# ME3116_3V3.net
KiCad netlist of a schematic drawn in Altium Designer
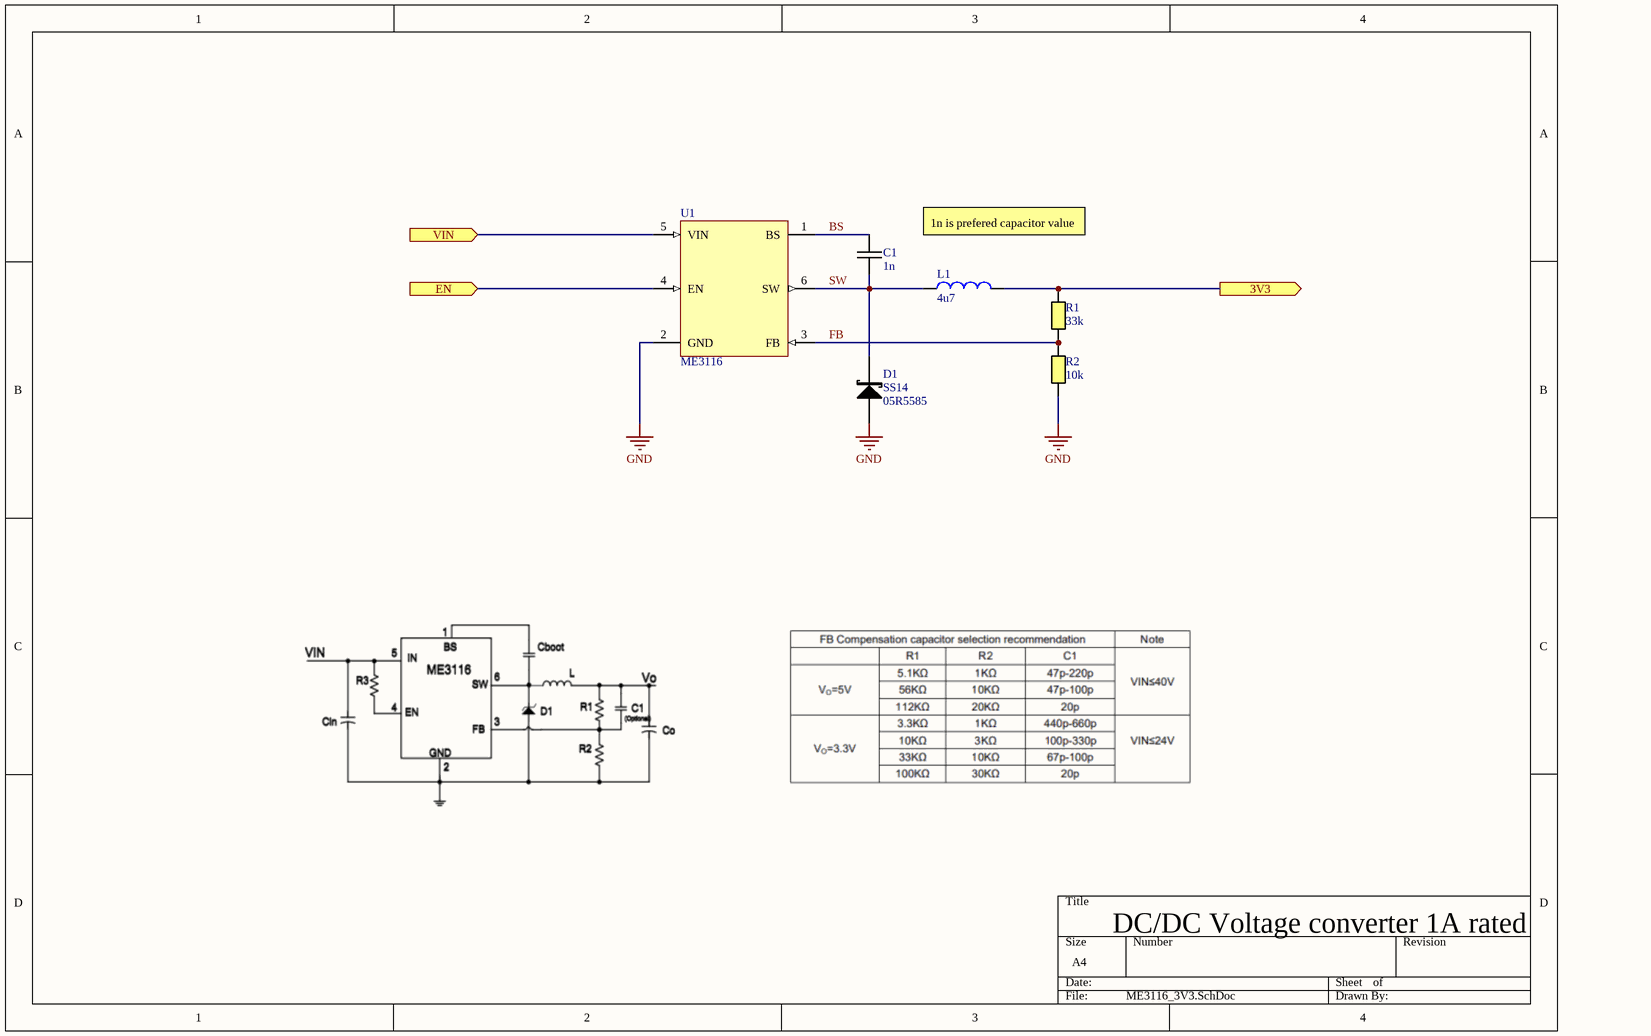
[diagram p0: ME3116_3V3.SchDoc]

(export (version "E")
  (design (tool "Eeschema 10.0.6"))
  (components
    (comp (ref "C1")
      (value "1n")
      (footprint "CAPC0603(1608)55_N")
      (description "Ceramic capacitor Medium density")
      (libsource (lib "Discrete") (part "Capacitor M"))
    )
    (comp (ref "D1")
      (value "SS14")
      (footprint "SMA")
      (description "Surface Mount Schottky Barrier Rectifier")
      (fields (field (name "SUPPLIER PART NUMBER 1") "05R5585"))
      (libsource (lib "Diodes") (part "SS14"))
    )
    (comp (ref "L1") (value "4u7") (footprint "CD75") (libsource (lib "Discrete") (part "Inductor")))
    (comp (ref "R1")
      (value "33k")
      (footprint "RESC0603(1608)_N")
      (description "Resistor Medium Density")
      (libsource (lib "Discrete") (part "Resistor M"))
    )
    (comp (ref "R2")
      (value "10k")
      (footprint "RESC0603(1608)_N")
      (description "Resistor Medium Density")
      (libsource (lib "Discrete") (part "Resistor M"))
    )
    (comp (ref "U1")
      (value "ME3116")
      (description "The ME3116 is PWM DC/DC buck (step-down) regulators.")
      (libsource (lib "VoltageRegulators") (part "ME3116"))
    )
  )
  (nets
    (net (code "1") (name "/3V3") (class "Default")
      (node (ref "L1") (pin "2") (pinfunction "2_2") (pintype "passive"))
      (node (ref "R1") (pin "2") (pinfunction "2_2") (pintype "passive"))
    )
    (net (code "2") (name "/BS") (class "Default")
      (node (ref "C1") (pin "1") (pinfunction "1_1") (pintype "passive"))
      (node (ref "U1") (pin "1") (pinfunction "BS_1") (pintype "passive"))
    )
    (net (code "3") (name "/EN") (class "Default")
      (node (ref "U1") (pin "4") (pinfunction "EN_4") (pintype "input"))
    )
    (net (code "4") (name "/FB") (class "Default")
      (node (ref "R1") (pin "1") (pinfunction "1_1") (pintype "passive"))
      (node (ref "R2") (pin "2") (pinfunction "2_2") (pintype "passive"))
      (node (ref "U1") (pin "3") (pinfunction "FB_3") (pintype "input"))
    )
    (net (code "5") (name "/SW") (class "Default")
      (node (ref "C1") (pin "2") (pinfunction "2_2") (pintype "passive"))
      (node (ref "D1") (pin "K") (pinfunction "K_K") (pintype "passive"))
      (node (ref "L1") (pin "1") (pinfunction "1_1") (pintype "passive"))
      (node (ref "U1") (pin "6") (pinfunction "SW_6") (pintype "output"))
    )
    (net (code "6") (name "/VIN") (class "Default")
      (node (ref "U1") (pin "5") (pinfunction "VIN_5") (pintype "input"))
    )
    (net (code "7") (name "GND") (class "Default")
      (node (ref "D1") (pin "A") (pinfunction "A_A") (pintype "passive"))
      (node (ref "R2") (pin "1") (pinfunction "1_1") (pintype "passive"))
      (node (ref "U1") (pin "2") (pinfunction "GND_2") (pintype "power_in"))
    )
  )
)
